# extensionboard.net
KiCad netlist of a schematic drawn in EAGLE
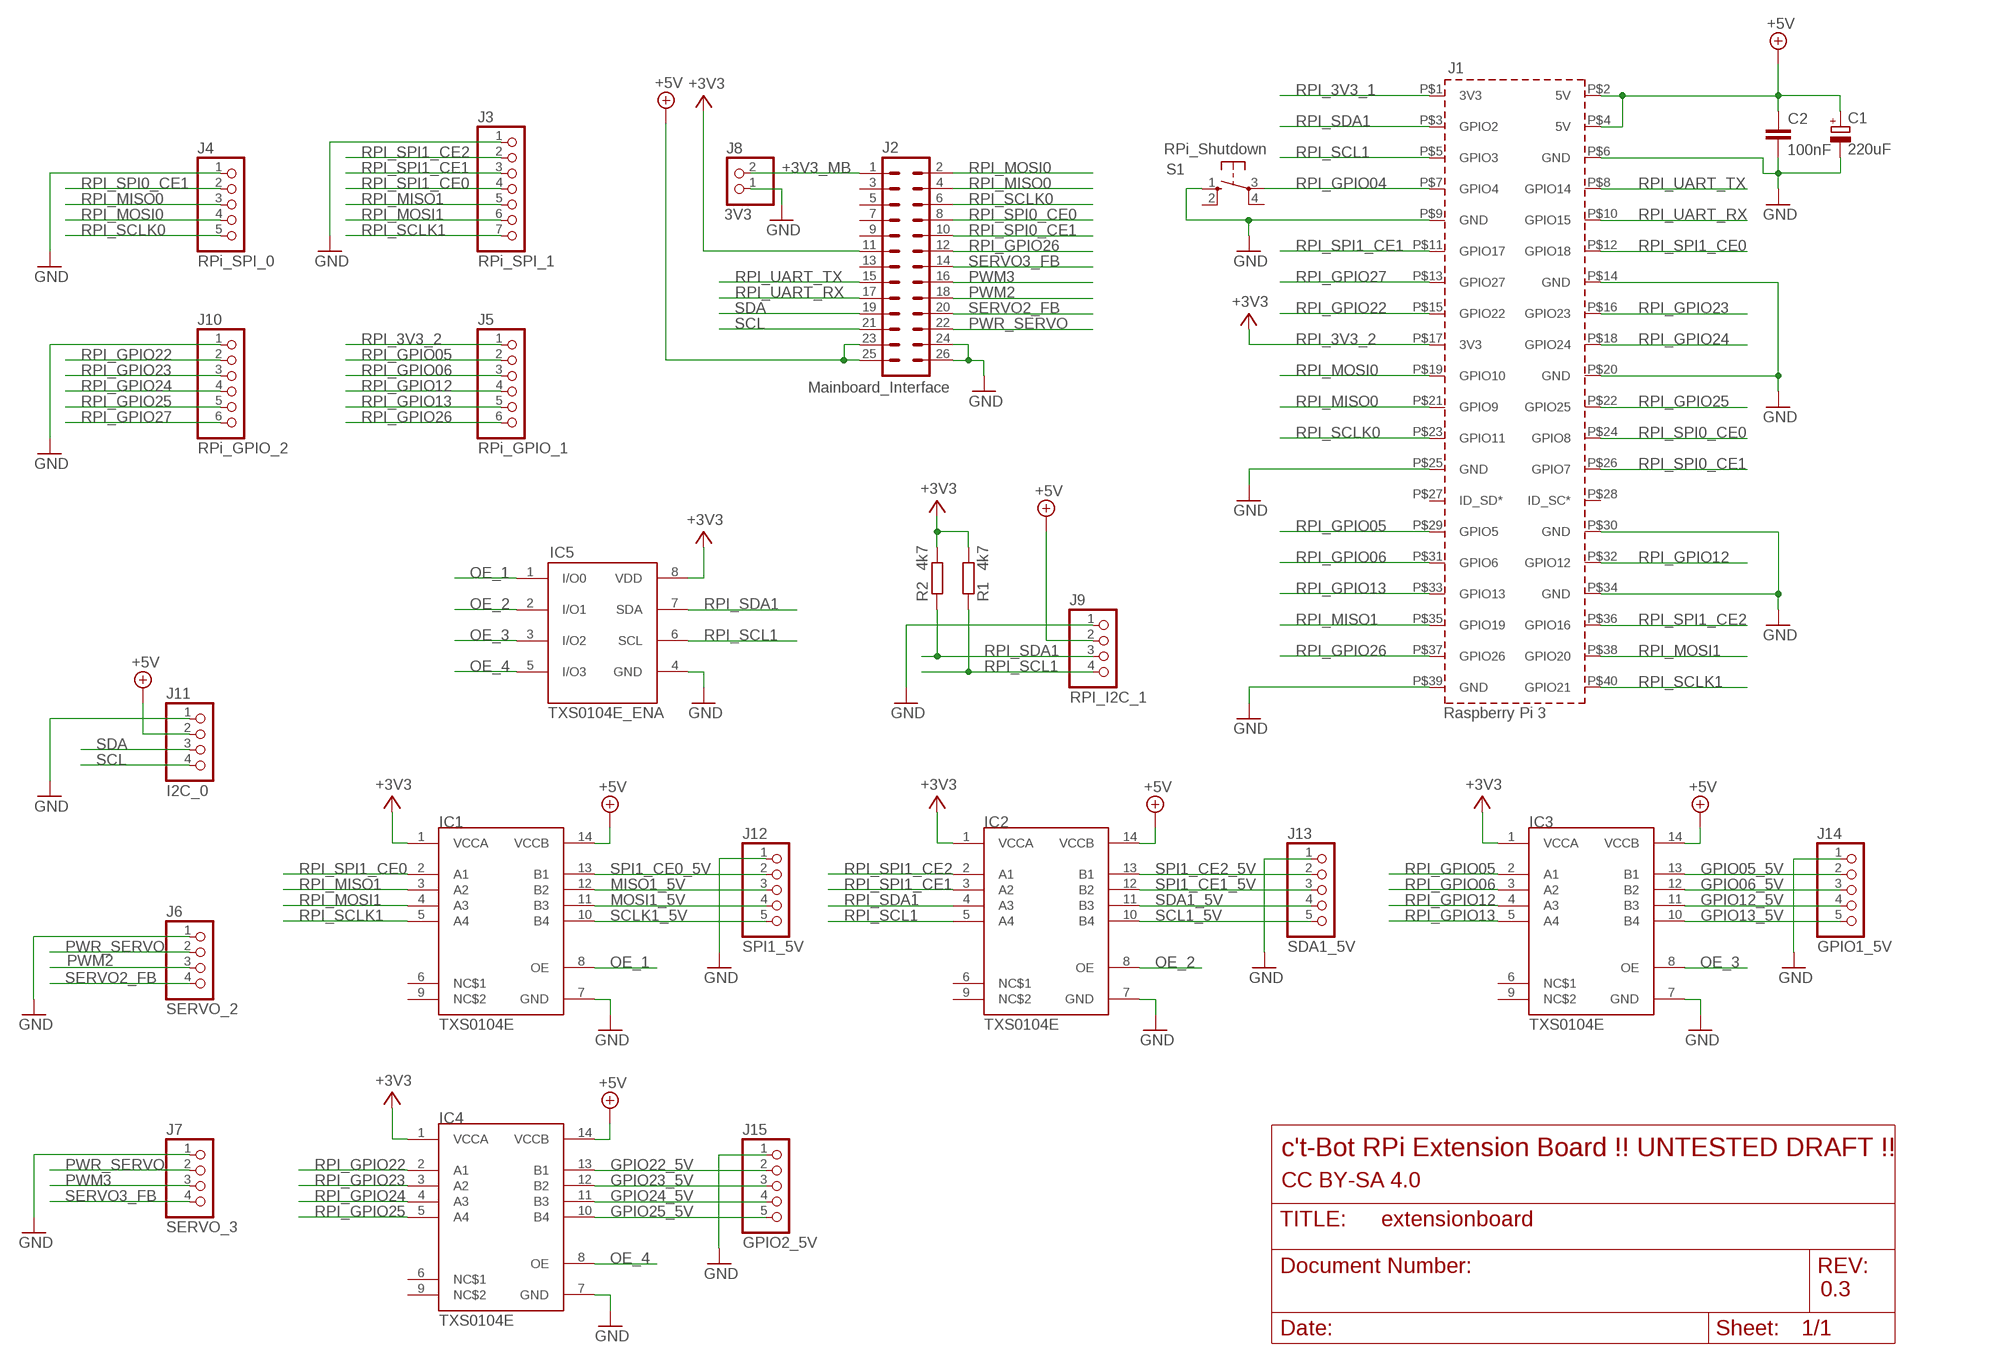
[diagram p0: schematic, sheet 1]

(export (version "E")
  (design (tool "Eeschema 10.0.6"))
  (components
    (comp (ref "C1")
      (value "220uF")
      (footprint "eagle-import:E2,5-6")
      (libsource (lib "eagle-import") (part "CPOL-EUE2.5-6"))
    )
    (comp (ref "C2")
      (value "100nF")
      (footprint "eagle-import:C025-024X044")
      (libsource (lib "eagle-import") (part "C-EU025-024X044"))
    )
    (comp (ref "IC1")
      (value "TXS0104E")
      (footprint "eagle-import:SO14")
      (libsource (lib "eagle-import") (part "TXS0104ED"))
    )
    (comp (ref "IC2")
      (value "TXS0104E")
      (footprint "eagle-import:SO14")
      (libsource (lib "eagle-import") (part "TXS0104ED"))
    )
    (comp (ref "IC3")
      (value "TXS0104E")
      (footprint "eagle-import:SO14")
      (libsource (lib "eagle-import") (part "TXS0104ED"))
    )
    (comp (ref "IC4")
      (value "TXS0104E")
      (footprint "eagle-import:SO14")
      (libsource (lib "eagle-import") (part "TXS0104ED"))
    )
    (comp (ref "IC5")
      (value "TXS0104E_ENA")
      (footprint "eagle-import:SOIC-8")
      (libsource (lib "eagle-import") (part "PCA9536D"))
    )
    (comp (ref "J1")
      (value "Raspberry Pi 3")
      (footprint "eagle-import:RPI3MIRROR")
      (libsource (lib "eagle-import") (part "RPI3RPI3MIRROR"))
    )
    (comp (ref "J2")
      (value "Mainboard_Interface")
      (footprint "eagle-import:ML26")
      (libsource (lib "eagle-import") (part "ML26"))
    )
    (comp (ref "J3")
      (value "RPi_SPI_1")
      (footprint "eagle-import:1X07")
      (libsource (lib "eagle-import") (part "PINHD-1X7"))
    )
    (comp (ref "J4")
      (value "RPi_SPI_0")
      (footprint "eagle-import:1X05")
      (libsource (lib "eagle-import") (part "PINHD-1X5"))
    )
    (comp (ref "J5")
      (value "RPi_GPIO_1")
      (footprint "eagle-import:1X06")
      (libsource (lib "eagle-import") (part "PINHD-1X6"))
    )
    (comp (ref "J6")
      (value "SERVO_2")
      (footprint "eagle-import:1X04")
      (libsource (lib "eagle-import") (part "PINHD-1X4"))
    )
    (comp (ref "J7")
      (value "SERVO_3")
      (footprint "eagle-import:1X04")
      (libsource (lib "eagle-import") (part "PINHD-1X4"))
    )
    (comp (ref "J8")
      (value "3V3")
      (footprint "eagle-import:1X02")
      (libsource (lib "eagle-import") (part "PINHD-1X2"))
    )
    (comp (ref "J9")
      (value "RPI_I2C_1")
      (footprint "eagle-import:1X04")
      (libsource (lib "eagle-import") (part "PINHD-1X4"))
    )
    (comp (ref "J10")
      (value "RPi_GPIO_2")
      (footprint "eagle-import:1X06")
      (libsource (lib "eagle-import") (part "PINHD-1X6"))
    )
    (comp (ref "J11")
      (value "I2C_0")
      (footprint "eagle-import:1X04")
      (libsource (lib "eagle-import") (part "PINHD-1X4"))
    )
    (comp (ref "J12")
      (value "SPI1_5V")
      (footprint "eagle-import:1X05")
      (libsource (lib "eagle-import") (part "PINHD-1X5"))
    )
    (comp (ref "J13")
      (value "SDA1_5V")
      (footprint "eagle-import:1X05")
      (libsource (lib "eagle-import") (part "PINHD-1X5"))
    )
    (comp (ref "J14")
      (value "GPIO1_5V")
      (footprint "eagle-import:1X05")
      (libsource (lib "eagle-import") (part "PINHD-1X5"))
    )
    (comp (ref "J15")
      (value "GPIO2_5V")
      (footprint "eagle-import:1X05")
      (libsource (lib "eagle-import") (part "PINHD-1X5"))
    )
    (comp (ref "R1")
      (value "4k7")
      (footprint "eagle-import:0204_7")
      (libsource (lib "eagle-import") (part "R-EU_0204/7"))
    )
    (comp (ref "R2")
      (value "4k7")
      (footprint "eagle-import:0204_7")
      (libsource (lib "eagle-import") (part "R-EU_0204/7"))
    )
    (comp (ref "S1")
      (value "RPi_Shutdown")
      (footprint "eagle-import:B3F-10XX")
      (fields (field (name "MPN") "B3F-1000"))
      (libsource (lib "eagle-import") (part "10-XX"))
    )
  )
  (nets
    (net (code "1") (name "+3V3") (class "Default")
      (node (ref "IC1") (pin "1") (pinfunction "VCCA_1") (pintype "power_in"))
      (node (ref "IC2") (pin "1") (pinfunction "VCCA_1") (pintype "power_in"))
      (node (ref "IC3") (pin "1") (pinfunction "VCCA_1") (pintype "power_in"))
      (node (ref "IC4") (pin "1") (pinfunction "VCCA_1") (pintype "power_in"))
      (node (ref "IC5") (pin "8") (pinfunction "VDD_8") (pintype "power_in"))
      (node (ref "J1") (pin "P$17") (pinfunction "3V3_P$17") (pintype "bidirectional"))
      (node (ref "J2") (pin "11") (pinfunction "11_11") (pintype "passive"))
      (node (ref "J5") (pin "1") (pinfunction "1_1") (pintype "passive"))
      (node (ref "R1") (pin "2") (pinfunction "2_2") (pintype "passive"))
      (node (ref "R2") (pin "2") (pinfunction "2_2") (pintype "passive"))
    )
    (net (code "2") (name "+5V") (class "Default")
      (node (ref "C1") (pin "+") (pinfunction "+_+") (pintype "passive"))
      (node (ref "C2") (pin "1") (pinfunction "1_1") (pintype "passive"))
      (node (ref "IC1") (pin "14") (pinfunction "VCCB_14") (pintype "power_in"))
      (node (ref "IC2") (pin "14") (pinfunction "VCCB_14") (pintype "power_in"))
      (node (ref "IC3") (pin "14") (pinfunction "VCCB_14") (pintype "power_in"))
      (node (ref "IC4") (pin "14") (pinfunction "VCCB_14") (pintype "power_in"))
      (node (ref "J1") (pin "P$2") (pinfunction "5V_P$2") (pintype "bidirectional"))
      (node (ref "J1") (pin "P$4") (pinfunction "5V_P$4") (pintype "bidirectional"))
      (node (ref "J11") (pin "2") (pinfunction "2_2") (pintype "passive"))
      (node (ref "J2") (pin "23") (pinfunction "23_23") (pintype "passive"))
      (node (ref "J2") (pin "25") (pinfunction "25_25") (pintype "passive"))
      (node (ref "J9") (pin "2") (pinfunction "2_2") (pintype "passive"))
    )
    (net (code "3") (name "/+3V3_MB") (class "Default")
      (node (ref "J2") (pin "1") (pinfunction "1_1") (pintype "passive"))
      (node (ref "J8") (pin "2") (pinfunction "2_2") (pintype "passive"))
    )
    (net (code "4") (name "/GPIO05_5V") (class "Default")
      (node (ref "IC3") (pin "13") (pinfunction "B1_13") (pintype "bidirectional"))
      (node (ref "J14") (pin "2") (pinfunction "2_2") (pintype "passive"))
    )
    (net (code "5") (name "/GPIO06_5V") (class "Default")
      (node (ref "IC3") (pin "12") (pinfunction "B2_12") (pintype "bidirectional"))
      (node (ref "J14") (pin "3") (pinfunction "3_3") (pintype "passive"))
    )
    (net (code "6") (name "/GPIO12_5V") (class "Default")
      (node (ref "IC3") (pin "11") (pinfunction "B3_11") (pintype "bidirectional"))
      (node (ref "J14") (pin "4") (pinfunction "4_4") (pintype "passive"))
    )
    (net (code "7") (name "/GPIO13_5V") (class "Default")
      (node (ref "IC3") (pin "10") (pinfunction "B4_10") (pintype "bidirectional"))
      (node (ref "J14") (pin "5") (pinfunction "5_5") (pintype "passive"))
    )
    (net (code "8") (name "/GPIO22_5V") (class "Default")
      (node (ref "IC4") (pin "13") (pinfunction "B1_13") (pintype "bidirectional"))
      (node (ref "J15") (pin "2") (pinfunction "2_2") (pintype "passive"))
    )
    (net (code "9") (name "/GPIO23_5V") (class "Default")
      (node (ref "IC4") (pin "12") (pinfunction "B2_12") (pintype "bidirectional"))
      (node (ref "J15") (pin "3") (pinfunction "3_3") (pintype "passive"))
    )
    (net (code "10") (name "/GPIO24_5V") (class "Default")
      (node (ref "IC4") (pin "11") (pinfunction "B3_11") (pintype "bidirectional"))
      (node (ref "J15") (pin "4") (pinfunction "4_4") (pintype "passive"))
    )
    (net (code "11") (name "/GPIO25_5V") (class "Default")
      (node (ref "IC4") (pin "10") (pinfunction "B4_10") (pintype "bidirectional"))
      (node (ref "J15") (pin "5") (pinfunction "5_5") (pintype "passive"))
    )
    (net (code "12") (name "/MISO1_5V") (class "Default")
      (node (ref "IC1") (pin "12") (pinfunction "B2_12") (pintype "bidirectional"))
      (node (ref "J12") (pin "3") (pinfunction "3_3") (pintype "passive"))
    )
    (net (code "13") (name "/MOSI1_5V") (class "Default")
      (node (ref "IC1") (pin "11") (pinfunction "B3_11") (pintype "bidirectional"))
      (node (ref "J12") (pin "4") (pinfunction "4_4") (pintype "passive"))
    )
    (net (code "14") (name "/OE_1") (class "Default")
      (node (ref "IC1") (pin "8") (pinfunction "OE_8") (pintype "input"))
      (node (ref "IC5") (pin "1") (pinfunction "I/O0_1") (pintype "bidirectional"))
    )
    (net (code "15") (name "/OE_2") (class "Default")
      (node (ref "IC2") (pin "8") (pinfunction "OE_8") (pintype "input"))
      (node (ref "IC5") (pin "2") (pinfunction "I/O1_2") (pintype "bidirectional"))
    )
    (net (code "16") (name "/OE_3") (class "Default")
      (node (ref "IC3") (pin "8") (pinfunction "OE_8") (pintype "input"))
      (node (ref "IC5") (pin "3") (pinfunction "I/O2_3") (pintype "bidirectional"))
    )
    (net (code "17") (name "/OE_4") (class "Default")
      (node (ref "IC4") (pin "8") (pinfunction "OE_8") (pintype "input"))
      (node (ref "IC5") (pin "5") (pinfunction "I/O3_5") (pintype "bidirectional"))
    )
    (net (code "18") (name "/PWM2") (class "Default")
      (node (ref "J2") (pin "18") (pinfunction "18_18") (pintype "passive"))
      (node (ref "J6") (pin "3") (pinfunction "3_3") (pintype "passive"))
    )
    (net (code "19") (name "/PWM3") (class "Default")
      (node (ref "J2") (pin "16") (pinfunction "16_16") (pintype "passive"))
      (node (ref "J7") (pin "3") (pinfunction "3_3") (pintype "passive"))
    )
    (net (code "20") (name "/PWR_SERVO") (class "Default")
      (node (ref "J2") (pin "22") (pinfunction "22_22") (pintype "passive"))
      (node (ref "J6") (pin "2") (pinfunction "2_2") (pintype "passive"))
      (node (ref "J7") (pin "2") (pinfunction "2_2") (pintype "passive"))
    )
    (net (code "21") (name "/RPI_3V3_1") (class "Default")
      (node (ref "J1") (pin "P$1") (pinfunction "3V3_P$1") (pintype "bidirectional"))
    )
    (net (code "22") (name "/RPI_GPIO04") (class "Default")
      (node (ref "J1") (pin "P$7") (pinfunction "GPIO4_P$7") (pintype "bidirectional"))
      (node (ref "S1") (pin "3") (pinfunction "P_3") (pintype "passive"))
    )
    (net (code "23") (name "/RPI_GPIO05") (class "Default")
      (node (ref "IC3") (pin "2") (pinfunction "A1_2") (pintype "bidirectional"))
      (node (ref "J1") (pin "P$29") (pinfunction "GPIO5_P$29") (pintype "bidirectional"))
      (node (ref "J5") (pin "2") (pinfunction "2_2") (pintype "passive"))
    )
    (net (code "24") (name "/RPI_GPIO06") (class "Default")
      (node (ref "IC3") (pin "3") (pinfunction "A2_3") (pintype "bidirectional"))
      (node (ref "J1") (pin "P$31") (pinfunction "GPIO6_P$31") (pintype "bidirectional"))
      (node (ref "J5") (pin "3") (pinfunction "3_3") (pintype "passive"))
    )
    (net (code "25") (name "/RPI_GPIO12") (class "Default")
      (node (ref "IC3") (pin "4") (pinfunction "A3_4") (pintype "bidirectional"))
      (node (ref "J1") (pin "P$32") (pinfunction "GPIO12_P$32") (pintype "bidirectional"))
      (node (ref "J5") (pin "4") (pinfunction "4_4") (pintype "passive"))
    )
    (net (code "26") (name "/RPI_GPIO13") (class "Default")
      (node (ref "IC3") (pin "5") (pinfunction "A4_5") (pintype "bidirectional"))
      (node (ref "J1") (pin "P$33") (pinfunction "GPIO13_P$33") (pintype "bidirectional"))
      (node (ref "J5") (pin "5") (pinfunction "5_5") (pintype "passive"))
    )
    (net (code "27") (name "/RPI_GPIO22") (class "Default")
      (node (ref "IC4") (pin "2") (pinfunction "A1_2") (pintype "bidirectional"))
      (node (ref "J1") (pin "P$15") (pinfunction "GPIO22_P$15") (pintype "bidirectional"))
      (node (ref "J10") (pin "2") (pinfunction "2_2") (pintype "passive"))
    )
    (net (code "28") (name "/RPI_GPIO23") (class "Default")
      (node (ref "IC4") (pin "3") (pinfunction "A2_3") (pintype "bidirectional"))
      (node (ref "J1") (pin "P$16") (pinfunction "GPIO23_P$16") (pintype "bidirectional"))
      (node (ref "J10") (pin "3") (pinfunction "3_3") (pintype "passive"))
    )
    (net (code "29") (name "/RPI_GPIO24") (class "Default")
      (node (ref "IC4") (pin "4") (pinfunction "A3_4") (pintype "bidirectional"))
      (node (ref "J1") (pin "P$18") (pinfunction "GPIO24_P$18") (pintype "bidirectional"))
      (node (ref "J10") (pin "4") (pinfunction "4_4") (pintype "passive"))
    )
    (net (code "30") (name "/RPI_GPIO25") (class "Default")
      (node (ref "IC4") (pin "5") (pinfunction "A4_5") (pintype "bidirectional"))
      (node (ref "J1") (pin "P$22") (pinfunction "GPIO25_P$22") (pintype "bidirectional"))
      (node (ref "J10") (pin "5") (pinfunction "5_5") (pintype "passive"))
    )
    (net (code "31") (name "/RPI_GPIO26") (class "Default")
      (node (ref "J1") (pin "P$37") (pinfunction "GPIO26_P$37") (pintype "bidirectional"))
      (node (ref "J2") (pin "12") (pinfunction "12_12") (pintype "passive"))
      (node (ref "J5") (pin "6") (pinfunction "6_6") (pintype "passive"))
    )
    (net (code "32") (name "/RPI_GPIO27") (class "Default")
      (node (ref "J1") (pin "P$13") (pinfunction "GPIO27_P$13") (pintype "bidirectional"))
      (node (ref "J10") (pin "6") (pinfunction "6_6") (pintype "passive"))
    )
    (net (code "33") (name "/RPI_MISO0") (class "Default")
      (node (ref "J1") (pin "P$21") (pinfunction "GPIO9_P$21") (pintype "bidirectional"))
      (node (ref "J2") (pin "4") (pinfunction "4_4") (pintype "passive"))
      (node (ref "J4") (pin "3") (pinfunction "3_3") (pintype "passive"))
    )
    (net (code "34") (name "/RPI_MISO1") (class "Default")
      (node (ref "IC1") (pin "3") (pinfunction "A2_3") (pintype "bidirectional"))
      (node (ref "J1") (pin "P$35") (pinfunction "GPIO19_P$35") (pintype "bidirectional"))
      (node (ref "J3") (pin "5") (pinfunction "5_5") (pintype "passive"))
    )
    (net (code "35") (name "/RPI_MOSI0") (class "Default")
      (node (ref "J1") (pin "P$19") (pinfunction "GPIO10_P$19") (pintype "bidirectional"))
      (node (ref "J2") (pin "2") (pinfunction "2_2") (pintype "passive"))
      (node (ref "J4") (pin "4") (pinfunction "4_4") (pintype "passive"))
    )
    (net (code "36") (name "/RPI_MOSI1") (class "Default")
      (node (ref "IC1") (pin "4") (pinfunction "A3_4") (pintype "bidirectional"))
      (node (ref "J1") (pin "P$38") (pinfunction "GPIO20_P$38") (pintype "bidirectional"))
      (node (ref "J3") (pin "6") (pinfunction "6_6") (pintype "passive"))
    )
    (net (code "37") (name "/RPI_SCL1") (class "Default")
      (node (ref "IC2") (pin "5") (pinfunction "A4_5") (pintype "bidirectional"))
      (node (ref "IC5") (pin "6") (pinfunction "SCL_6") (pintype "bidirectional"))
      (node (ref "J1") (pin "P$5") (pinfunction "GPIO3_P$5") (pintype "bidirectional"))
      (node (ref "J9") (pin "4") (pinfunction "4_4") (pintype "passive"))
      (node (ref "R1") (pin "1") (pinfunction "1_1") (pintype "passive"))
    )
    (net (code "38") (name "/RPI_SCLK0") (class "Default")
      (node (ref "J1") (pin "P$23") (pinfunction "GPIO11_P$23") (pintype "bidirectional"))
      (node (ref "J2") (pin "6") (pinfunction "6_6") (pintype "passive"))
      (node (ref "J4") (pin "5") (pinfunction "5_5") (pintype "passive"))
    )
    (net (code "39") (name "/RPI_SCLK1") (class "Default")
      (node (ref "IC1") (pin "5") (pinfunction "A4_5") (pintype "bidirectional"))
      (node (ref "J1") (pin "P$40") (pinfunction "GPIO21_P$40") (pintype "bidirectional"))
      (node (ref "J3") (pin "7") (pinfunction "7_7") (pintype "passive"))
    )
    (net (code "40") (name "/RPI_SDA1") (class "Default")
      (node (ref "IC2") (pin "4") (pinfunction "A3_4") (pintype "bidirectional"))
      (node (ref "IC5") (pin "7") (pinfunction "SDA_7") (pintype "bidirectional"))
      (node (ref "J1") (pin "P$3") (pinfunction "GPIO2_P$3") (pintype "bidirectional"))
      (node (ref "J9") (pin "3") (pinfunction "3_3") (pintype "passive"))
      (node (ref "R2") (pin "1") (pinfunction "1_1") (pintype "passive"))
    )
    (net (code "41") (name "/RPI_SPI0_CE0") (class "Default")
      (node (ref "J1") (pin "P$24") (pinfunction "GPIO8_P$24") (pintype "bidirectional"))
      (node (ref "J2") (pin "8") (pinfunction "8_8") (pintype "passive"))
    )
    (net (code "42") (name "/RPI_SPI0_CE1") (class "Default")
      (node (ref "J1") (pin "P$26") (pinfunction "GPIO7_P$26") (pintype "bidirectional"))
      (node (ref "J2") (pin "10") (pinfunction "10_10") (pintype "passive"))
      (node (ref "J4") (pin "2") (pinfunction "2_2") (pintype "passive"))
    )
    (net (code "43") (name "/RPI_SPI1_CE0") (class "Default")
      (node (ref "IC1") (pin "2") (pinfunction "A1_2") (pintype "bidirectional"))
      (node (ref "J1") (pin "P$12") (pinfunction "GPIO18_P$12") (pintype "bidirectional"))
      (node (ref "J3") (pin "4") (pinfunction "4_4") (pintype "passive"))
    )
    (net (code "44") (name "/RPI_SPI1_CE1") (class "Default")
      (node (ref "IC2") (pin "3") (pinfunction "A2_3") (pintype "bidirectional"))
      (node (ref "J1") (pin "P$11") (pinfunction "GPIO17_P$11") (pintype "bidirectional"))
      (node (ref "J3") (pin "3") (pinfunction "3_3") (pintype "passive"))
    )
    (net (code "45") (name "/RPI_SPI1_CE2") (class "Default")
      (node (ref "IC2") (pin "2") (pinfunction "A1_2") (pintype "bidirectional"))
      (node (ref "J1") (pin "P$36") (pinfunction "GPIO16_P$36") (pintype "bidirectional"))
      (node (ref "J3") (pin "2") (pinfunction "2_2") (pintype "passive"))
    )
    (net (code "46") (name "/RPI_UART_RX") (class "Default")
      (node (ref "J1") (pin "P$10") (pinfunction "GPIO15_P$10") (pintype "bidirectional"))
      (node (ref "J2") (pin "17") (pinfunction "17_17") (pintype "passive"))
    )
    (net (code "47") (name "/RPI_UART_TX") (class "Default")
      (node (ref "J1") (pin "P$8") (pinfunction "GPIO14_P$8") (pintype "bidirectional"))
      (node (ref "J2") (pin "15") (pinfunction "15_15") (pintype "passive"))
    )
    (net (code "48") (name "/SCL") (class "Default")
      (node (ref "J11") (pin "4") (pinfunction "4_4") (pintype "passive"))
      (node (ref "J2") (pin "21") (pinfunction "21_21") (pintype "passive"))
    )
    (net (code "49") (name "/SCL1_5V") (class "Default")
      (node (ref "IC2") (pin "10") (pinfunction "B4_10") (pintype "bidirectional"))
      (node (ref "J13") (pin "5") (pinfunction "5_5") (pintype "passive"))
    )
    (net (code "50") (name "/SCLK1_5V") (class "Default")
      (node (ref "IC1") (pin "10") (pinfunction "B4_10") (pintype "bidirectional"))
      (node (ref "J12") (pin "5") (pinfunction "5_5") (pintype "passive"))
    )
    (net (code "51") (name "/SDA") (class "Default")
      (node (ref "J11") (pin "3") (pinfunction "3_3") (pintype "passive"))
      (node (ref "J2") (pin "19") (pinfunction "19_19") (pintype "passive"))
    )
    (net (code "52") (name "/SDA1_5V") (class "Default")
      (node (ref "IC2") (pin "11") (pinfunction "B3_11") (pintype "bidirectional"))
      (node (ref "J13") (pin "4") (pinfunction "4_4") (pintype "passive"))
    )
    (net (code "53") (name "/SERVO2_FB") (class "Default")
      (node (ref "J2") (pin "20") (pinfunction "20_20") (pintype "passive"))
      (node (ref "J6") (pin "4") (pinfunction "4_4") (pintype "passive"))
    )
    (net (code "54") (name "/SERVO3_FB") (class "Default")
      (node (ref "J2") (pin "14") (pinfunction "14_14") (pintype "passive"))
      (node (ref "J7") (pin "4") (pinfunction "4_4") (pintype "passive"))
    )
    (net (code "55") (name "/SPI1_CE0_5V") (class "Default")
      (node (ref "IC1") (pin "13") (pinfunction "B1_13") (pintype "bidirectional"))
      (node (ref "J12") (pin "2") (pinfunction "2_2") (pintype "passive"))
    )
    (net (code "56") (name "/SPI1_CE1_5V") (class "Default")
      (node (ref "IC2") (pin "12") (pinfunction "B2_12") (pintype "bidirectional"))
      (node (ref "J13") (pin "3") (pinfunction "3_3") (pintype "passive"))
    )
    (net (code "57") (name "/SPI1_CE2_5V") (class "Default")
      (node (ref "IC2") (pin "13") (pinfunction "B1_13") (pintype "bidirectional"))
      (node (ref "J13") (pin "2") (pinfunction "2_2") (pintype "passive"))
    )
    (net (code "58") (name "GND") (class "Default")
      (node (ref "C1") (pin "-") (pinfunction "-_-") (pintype "passive"))
      (node (ref "C2") (pin "2") (pinfunction "2_2") (pintype "passive"))
      (node (ref "IC1") (pin "7") (pinfunction "GND_7") (pintype "power_in"))
      (node (ref "IC2") (pin "7") (pinfunction "GND_7") (pintype "power_in"))
      (node (ref "IC3") (pin "7") (pinfunction "GND_7") (pintype "power_in"))
      (node (ref "IC4") (pin "7") (pinfunction "GND_7") (pintype "power_in"))
      (node (ref "IC5") (pin "4") (pinfunction "GND_4") (pintype "power_in"))
      (node (ref "J1") (pin "P$14") (pinfunction "GND_P$14") (pintype "bidirectional"))
      (node (ref "J1") (pin "P$20") (pinfunction "GND_P$20") (pintype "bidirectional"))
      (node (ref "J1") (pin "P$25") (pinfunction "GND_P$25") (pintype "bidirectional"))
      (node (ref "J1") (pin "P$30") (pinfunction "GND_P$30") (pintype "bidirectional"))
      (node (ref "J1") (pin "P$34") (pinfunction "GND_P$34") (pintype "bidirectional"))
      (node (ref "J1") (pin "P$39") (pinfunction "GND_P$39") (pintype "bidirectional"))
      (node (ref "J1") (pin "P$6") (pinfunction "GND_P$6") (pintype "bidirectional"))
      (node (ref "J1") (pin "P$9") (pinfunction "GND_P$9") (pintype "bidirectional"))
      (node (ref "J10") (pin "1") (pinfunction "1_1") (pintype "passive"))
      (node (ref "J11") (pin "1") (pinfunction "1_1") (pintype "passive"))
      (node (ref "J12") (pin "1") (pinfunction "1_1") (pintype "passive"))
      (node (ref "J13") (pin "1") (pinfunction "1_1") (pintype "passive"))
      (node (ref "J14") (pin "1") (pinfunction "1_1") (pintype "passive"))
      (node (ref "J15") (pin "1") (pinfunction "1_1") (pintype "passive"))
      (node (ref "J2") (pin "24") (pinfunction "24_24") (pintype "passive"))
      (node (ref "J2") (pin "26") (pinfunction "26_26") (pintype "passive"))
      (node (ref "J3") (pin "1") (pinfunction "1_1") (pintype "passive"))
      (node (ref "J4") (pin "1") (pinfunction "1_1") (pintype "passive"))
      (node (ref "J6") (pin "1") (pinfunction "1_1") (pintype "passive"))
      (node (ref "J7") (pin "1") (pinfunction "1_1") (pintype "passive"))
      (node (ref "J8") (pin "1") (pinfunction "1_1") (pintype "passive"))
      (node (ref "J9") (pin "1") (pinfunction "1_1") (pintype "passive"))
      (node (ref "S1") (pin "1") (pinfunction "S_1") (pintype "passive"))
    )
    (net (code "59") (name "unconnected-(IC1-NC$1-Pad6)") (class "Default")
      (node (ref "IC1") (pin "6") (pinfunction "NC$1_6") (pintype "no_connect"))
    )
    (net (code "60") (name "unconnected-(IC1-NC$2-Pad9)") (class "Default")
      (node (ref "IC1") (pin "9") (pinfunction "NC$2_9") (pintype "no_connect"))
    )
    (net (code "61") (name "unconnected-(IC2-NC$1-Pad6)") (class "Default")
      (node (ref "IC2") (pin "6") (pinfunction "NC$1_6") (pintype "no_connect"))
    )
    (net (code "62") (name "unconnected-(IC2-NC$2-Pad9)") (class "Default")
      (node (ref "IC2") (pin "9") (pinfunction "NC$2_9") (pintype "no_connect"))
    )
    (net (code "63") (name "unconnected-(IC3-NC$1-Pad6)") (class "Default")
      (node (ref "IC3") (pin "6") (pinfunction "NC$1_6") (pintype "no_connect"))
    )
    (net (code "64") (name "unconnected-(IC3-NC$2-Pad9)") (class "Default")
      (node (ref "IC3") (pin "9") (pinfunction "NC$2_9") (pintype "no_connect"))
    )
    (net (code "65") (name "unconnected-(IC4-NC$1-Pad6)") (class "Default")
      (node (ref "IC4") (pin "6") (pinfunction "NC$1_6") (pintype "no_connect"))
    )
    (net (code "66") (name "unconnected-(IC4-NC$2-Pad9)") (class "Default")
      (node (ref "IC4") (pin "9") (pinfunction "NC$2_9") (pintype "no_connect"))
    )
    (net (code "67") (name "unconnected-(J1-ID_SC*-PadP$28)") (class "Default")
      (node (ref "J1") (pin "P$28") (pinfunction "ID_SC*_P$28") (pintype "bidirectional"))
    )
    (net (code "68") (name "unconnected-(J1-ID_SD*-PadP$27)") (class "Default")
      (node (ref "J1") (pin "P$27") (pinfunction "ID_SD*_P$27") (pintype "bidirectional"))
    )
    (net (code "69") (name "unconnected-(J2-Pad3)") (class "Default")
      (node (ref "J2") (pin "3") (pinfunction "3_3") (pintype "passive"))
    )
    (net (code "70") (name "unconnected-(J2-Pad5)") (class "Default")
      (node (ref "J2") (pin "5") (pinfunction "5_5") (pintype "passive"))
    )
    (net (code "71") (name "unconnected-(J2-Pad7)") (class "Default")
      (node (ref "J2") (pin "7") (pinfunction "7_7") (pintype "passive"))
    )
    (net (code "72") (name "unconnected-(J2-Pad9)") (class "Default")
      (node (ref "J2") (pin "9") (pinfunction "9_9") (pintype "passive"))
    )
    (net (code "73") (name "unconnected-(J2-Pad13)") (class "Default")
      (node (ref "J2") (pin "13") (pinfunction "13_13") (pintype "passive"))
    )
    (net (code "74") (name "unconnected-(S1-P1-Pad4)") (class "Default")
      (node (ref "S1") (pin "4") (pinfunction "P1_4") (pintype "passive"))
    )
    (net (code "75") (name "unconnected-(S1-S1-Pad2)") (class "Default")
      (node (ref "S1") (pin "2") (pinfunction "S1_2") (pintype "passive"))
    )
  )
)
